# regulator.net
KiCad netlist of a schematic drawn in EAGLE
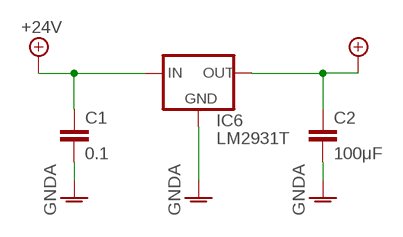
[diagram p0: schematic, sheet 1]

(export (version "E")
  (design (tool "Eeschema 10.0.6"))
  (components
    (comp (ref "C1")
      (value "0.1")
      (footprint "eagle-import:C2.5-3")
      (libsource (lib "eagle-import") (part "C2,5-3"))
    )
    (comp (ref "C2")
      (value "100μF")
      (footprint "eagle-import:C2.5-3")
      (libsource (lib "eagle-import") (part "C2,5-3"))
    )
    (comp (ref "IC6")
      (value "LM2931T")
      (footprint "eagle-import:TO220S")
      (libsource (lib "eagle-import") (part "LM2931T"))
    )
  )
  (nets
    (net (code "1") (name "+5V") (class "Default")
      (node (ref "C2") (pin "1") (pinfunction "1_1") (pintype "passive"))
      (node (ref "IC6") (pin "3") (pinfunction "OUT_3") (pintype "passive"))
    )
    (net (code "2") (name "+24V") (class "Default")
      (node (ref "C1") (pin "1") (pinfunction "1_1") (pintype "passive"))
      (node (ref "IC6") (pin "1") (pinfunction "IN_1") (pintype "input"))
    )
    (net (code "3") (name "GNDA") (class "Default")
      (node (ref "C1") (pin "2") (pinfunction "2_2") (pintype "passive"))
      (node (ref "C2") (pin "2") (pinfunction "2_2") (pintype "passive"))
      (node (ref "IC6") (pin "2") (pinfunction "GND_2") (pintype "input"))
    )
  )
)
